# hallpcb.net
KiCad netlist of a schematic drawn in Altium Designer
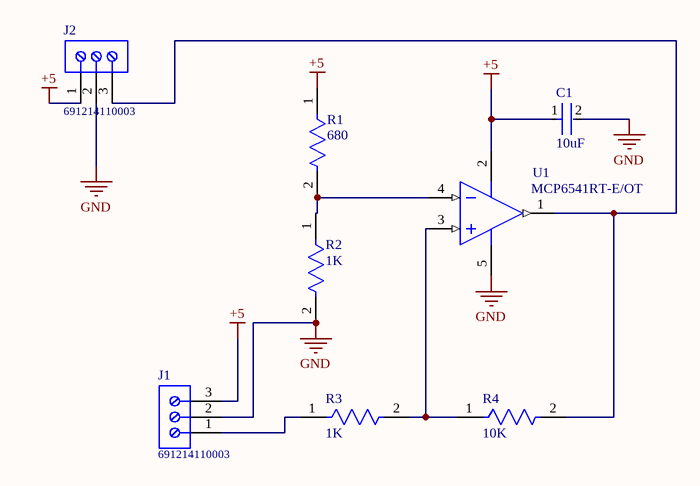
[diagram p0: hallpcb.SchDoc]

(export (version "E")
  (design (tool "Eeschema 10.0.6"))
  (components
    (comp (ref "C1")
      (value "10uF")
      (footprint "FP-CC1206-1_25-MFG")
      (description "CAP CER 0.1UF 50V X7R 1206")
      (fields
        (field (name "OCTOPART") "https://octopart.com/cc1206krx7r9bb104-yageo-39467816")
        (field (name "TOLERANCE") "0.1")
      )
      (libsource (lib "Altium Content Vault") (part "11868f565c42a9108669ba33697ecf6"))
    )
    (comp (ref "J1")
      (value "691214110003")
      (footprint "691214110003")
      (description "Serie 2141 - 3.50 mm Horizontal Entry Modular with Rising Cage Clamp WR-TBL, 3 pin")
      (fields (field (name "MANUFACTURER") "Wurth Elektronik") (field (name "PUBLISHER") "WurthElektronik"))
      (libsource (lib "Altium Content Vault") (part "WE-CN-1P-F-TB3"))
    )
    (comp (ref "J2")
      (value "691214110003")
      (footprint "691214110003")
      (description "Serie 2141 - 3.50 mm Horizontal Entry Modular with Rising Cage Clamp WR-TBL, 3 pin")
      (fields (field (name "MANUFACTURER") "Wurth Elektronik") (field (name "PUBLISHER") "WurthElektronik"))
      (libsource (lib "Altium Content Vault") (part "WE-CN-1P-F-TB3"))
    )
    (comp (ref "R1")
      (value "680")
      (footprint "FP-CRCW1206-e3-IPC_C")
      (description "RES Thick Film, 0Ω, 0.25W, 1206")
      (fields (field (name "TOLERANCE") "1%"))
      (libsource (lib "Altium Content Vault") (part "1029c3af85768c4190bb7ad29bc67b5"))
    )
    (comp (ref "R2")
      (value "1K")
      (footprint "FP-CRCW1206-e3-IPC_C")
      (description "RES Thick Film, 0Ω, 0.25W, 1206")
      (fields (field (name "TOLERANCE") "1%"))
      (libsource (lib "Altium Content Vault") (part "1029c3af85768c4190bb7ad29bc67b5"))
    )
    (comp (ref "R3")
      (value "1K")
      (footprint "FP-CRCW1206-e3-IPC_C")
      (description "RES Thick Film, 0Ω, 0.25W, 1206")
      (fields (field (name "TOLERANCE") "1%"))
      (libsource (lib "Altium Content Vault") (part "1029c3af85768c4190bb7ad29bc67b5"))
    )
    (comp (ref "R4")
      (value "10K")
      (footprint "FP-CRCW1206-e3-IPC_C")
      (description "RES Thick Film, 0Ω, 0.25W, 1206")
      (fields (field (name "TOLERANCE") "1%"))
      (libsource (lib "Altium Content Vault") (part "1029c3af85768c4190bb7ad29bc67b5"))
    )
    (comp (ref "U1")
      (value "MCP6541RT-E/OT")
      (footprint "SOT-23-OT5_M")
      (description "None")
      (libsource (lib "Altium Content Vault") (part "LO-COMP-MCP6541R-SOT5"))
    )
  )
  (nets
    (net (code "1") (name "+5") (class "Default")
      (node (ref "C1") (pin "1") (pinfunction "1_1") (pintype "passive"))
      (node (ref "J1") (pin "3") (pinfunction "3_3") (pintype "passive"))
      (node (ref "J2") (pin "1") (pinfunction "1_1") (pintype "passive"))
      (node (ref "R1") (pin "1") (pinfunction "1_1") (pintype "passive"))
      (node (ref "U1") (pin "2") (pinfunction "VDD_2") (pintype "power_in"))
    )
    (net (code "2") (name "GND") (class "Default")
      (node (ref "C1") (pin "2") (pinfunction "2_2") (pintype "passive"))
      (node (ref "J1") (pin "2") (pinfunction "2_2") (pintype "passive"))
      (node (ref "J2") (pin "2") (pinfunction "2_2") (pintype "passive"))
      (node (ref "R2") (pin "2") (pinfunction "2_2") (pintype "passive"))
      (node (ref "U1") (pin "5") (pinfunction "VSS_5") (pintype "power_in"))
    )
    (net (code "3") (name "Net-(J1-Pad1)") (class "Default")
      (node (ref "J1") (pin "1") (pinfunction "1_1") (pintype "passive"))
      (node (ref "R3") (pin "1") (pinfunction "1_1") (pintype "passive"))
    )
    (net (code "4") (name "Net-(U1-OUT)") (class "Default")
      (node (ref "J2") (pin "3") (pinfunction "3_3") (pintype "passive"))
      (node (ref "R4") (pin "2") (pinfunction "2_2") (pintype "passive"))
      (node (ref "U1") (pin "1") (pinfunction "OUT_1") (pintype "output"))
    )
    (net (code "5") (name "Net-(U1-VIN+)") (class "Default")
      (node (ref "R3") (pin "2") (pinfunction "2_2") (pintype "passive"))
      (node (ref "R4") (pin "1") (pinfunction "1_1") (pintype "passive"))
      (node (ref "U1") (pin "3") (pinfunction "VIN+_3") (pintype "input"))
    )
    (net (code "6") (name "Net-(U1-VIN-)") (class "Default")
      (node (ref "R1") (pin "2") (pinfunction "2_2") (pintype "passive"))
      (node (ref "R2") (pin "1") (pinfunction "1_1") (pintype "passive"))
      (node (ref "U1") (pin "4") (pinfunction "VIN-_4") (pintype "input"))
    )
  )
)
